# button_board_v0_3_3.net
KiCad netlist of a schematic drawn in EAGLE
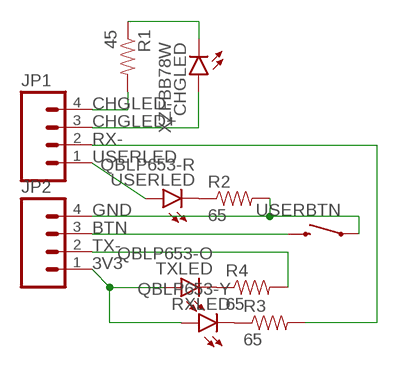
[diagram p0: schematic, sheet 1]

(export (version "E")
  (design (tool "Eeschema 10.0.6"))
  (components
    (comp (ref "CHGLED")
      (value "XZFBB78W")
      (footprint "eagle-import:LED-1208")
      (libsource (lib "eagle-import") (part "LED1208"))
    )
    (comp (ref "JP1")
      (value "M04PTH")
      (footprint "eagle-import:1X04")
      (libsource (lib "eagle-import") (part "M04PTH"))
    )
    (comp (ref "JP2")
      (value "M04PTH")
      (footprint "eagle-import:1X04")
      (libsource (lib "eagle-import") (part "M04PTH"))
    )
    (comp (ref "R1")
      (value "45")
      (footprint "eagle-import:0603-RES")
      (libsource (lib "eagle-import") (part "RESISTOR0603-RES"))
    )
    (comp (ref "R2")
      (value "65")
      (footprint "eagle-import:0603-RES")
      (libsource (lib "eagle-import") (part "RESISTOR0603-RES"))
    )
    (comp (ref "R3")
      (value "65")
      (footprint "eagle-import:0603-RES")
      (libsource (lib "eagle-import") (part "RESISTOR0603-RES"))
    )
    (comp (ref "R4")
      (value "65")
      (footprint "eagle-import:0603-RES")
      (libsource (lib "eagle-import") (part "RESISTOR0603-RES"))
    )
    (comp (ref "RXLED")
      (value "QBLP653-Y")
      (footprint "eagle-import:LED-1208")
      (libsource (lib "eagle-import") (part "LED1208"))
    )
    (comp (ref "TXLED")
      (value "QBLP653-O")
      (footprint "eagle-import:LED-1208")
      (libsource (lib "eagle-import") (part "LED1208"))
    )
    (comp (ref "USERBTN")
      (value "SWITCH-MOMENTARY-2PCB_MOUNTSMD_OMRON_B3S_100X")
      (footprint "eagle-import:TACTILE_SWITCH_LARGE")
      (libsource (lib "eagle-import") (part "SWITCH-MOMENTARY-2SMD_OMRON_B3S_100XPCB_MOUNT"))
    )
    (comp (ref "USERLED")
      (value "QBLP653-R")
      (footprint "eagle-import:LED-1208")
      (libsource (lib "eagle-import") (part "LED1208"))
    )
  )
  (nets
    (net (code "1") (name "/3V3") (class "Default")
      (node (ref "JP2") (pin "1") (pinfunction "1_1") (pintype "passive"))
      (node (ref "RXLED") (pin "A") (pinfunction "A_A") (pintype "passive"))
      (node (ref "TXLED") (pin "A") (pinfunction "A_A") (pintype "passive"))
    )
    (net (code "2") (name "/BTN") (class "Default")
      (node (ref "JP2") (pin "3") (pinfunction "3_3") (pintype "passive"))
      (node (ref "USERBTN") (pin "3") (pinfunction "2_3") (pintype "passive"))
      (node (ref "USERBTN") (pin "4") (pinfunction "2_4") (pintype "passive"))
    )
    (net (code "3") (name "/CHGLED+") (class "Default")
      (node (ref "CHGLED") (pin "A") (pinfunction "A_A") (pintype "passive"))
      (node (ref "JP1") (pin "3") (pinfunction "3_3") (pintype "passive"))
    )
    (net (code "4") (name "/CHGLED-") (class "Default")
      (node (ref "JP1") (pin "4") (pinfunction "4_4") (pintype "passive"))
      (node (ref "R1") (pin "2") (pinfunction "2_2") (pintype "passive"))
    )
    (net (code "5") (name "/GND") (class "Default")
      (node (ref "JP2") (pin "4") (pinfunction "4_4") (pintype "passive"))
      (node (ref "R2") (pin "2") (pinfunction "2_2") (pintype "passive"))
      (node (ref "USERBTN") (pin "1") (pinfunction "1_1") (pintype "passive"))
      (node (ref "USERBTN") (pin "2") (pinfunction "1_2") (pintype "passive"))
    )
    (net (code "6") (name "/RX-") (class "Default")
      (node (ref "JP1") (pin "2") (pinfunction "2_2") (pintype "passive"))
      (node (ref "R3") (pin "2") (pinfunction "2_2") (pintype "passive"))
    )
    (net (code "7") (name "/TX-") (class "Default")
      (node (ref "JP2") (pin "2") (pinfunction "2_2") (pintype "passive"))
      (node (ref "R4") (pin "2") (pinfunction "2_2") (pintype "passive"))
    )
    (net (code "8") (name "/USERLED") (class "Default")
      (node (ref "JP1") (pin "1") (pinfunction "1_1") (pintype "passive"))
      (node (ref "USERLED") (pin "A") (pinfunction "A_A") (pintype "passive"))
    )
    (net (code "9") (name "Net-(CHGLED-PadC)") (class "Default")
      (node (ref "CHGLED") (pin "C") (pinfunction "C_C") (pintype "passive"))
      (node (ref "R1") (pin "1") (pinfunction "1_1") (pintype "passive"))
    )
    (net (code "10") (name "Net-(R2-Pad1)") (class "Default")
      (node (ref "R2") (pin "1") (pinfunction "1_1") (pintype "passive"))
      (node (ref "USERLED") (pin "C") (pinfunction "C_C") (pintype "passive"))
    )
    (net (code "11") (name "Net-(R3-Pad1)") (class "Default")
      (node (ref "R3") (pin "1") (pinfunction "1_1") (pintype "passive"))
      (node (ref "RXLED") (pin "C") (pinfunction "C_C") (pintype "passive"))
    )
    (net (code "12") (name "Net-(R4-Pad1)") (class "Default")
      (node (ref "R4") (pin "1") (pinfunction "1_1") (pintype "passive"))
      (node (ref "TXLED") (pin "C") (pinfunction "C_C") (pintype "passive"))
    )
  )
)
